# Sheet1.net
KiCad netlist of a schematic drawn in Altium Designer
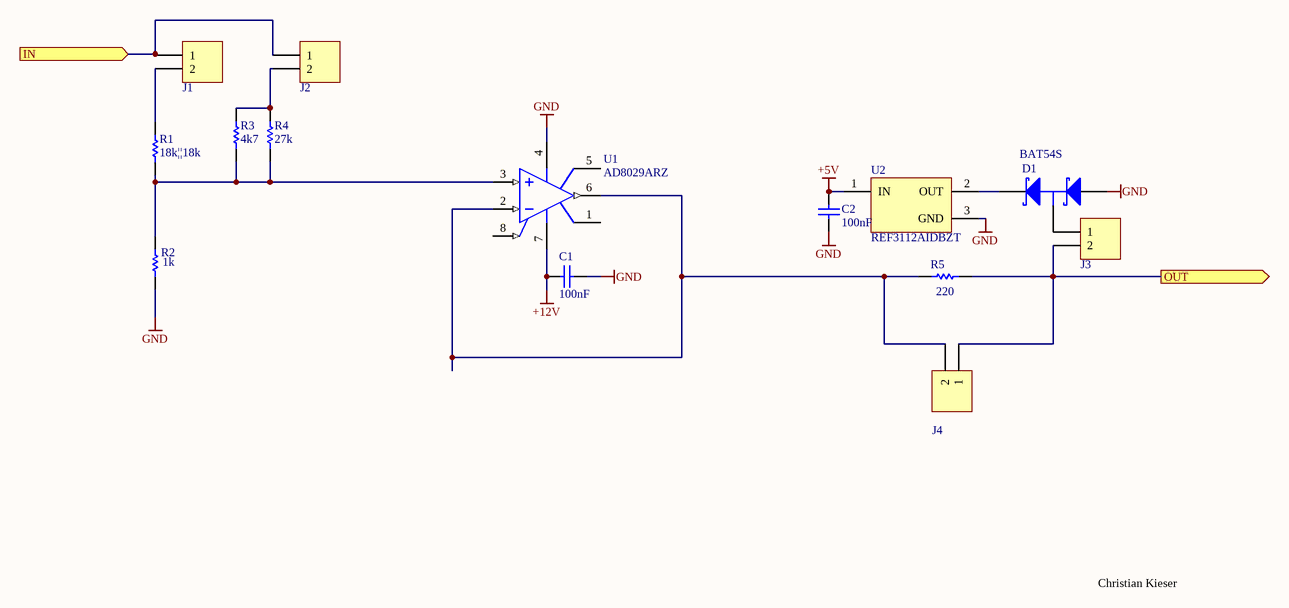
[diagram p0: Sheet1.SchDoc]

(export (version "E")
  (design (tool "Eeschema 10.0.6"))
  (components
    (comp (ref "C1")
      (value "100nF")
      (footprint "CAPC2013X88X50ML20T25")
      (description "generic 0805 COG oder X7R Vielschichtkondensatoren max. +/-10%")
      (libsource (lib "Altium Vault EMBL") (part "CMP-001-0082-2"))
    )
    (comp (ref "C2")
      (value "100nF")
      (footprint "CAPC2013X88X50ML20T25")
      (description "generic 0805 COG oder X7R Vielschichtkondensatoren max. +/-10%")
      (libsource (lib "Altium Vault EMBL") (part "CMP-001-0082-2"))
    )
    (comp (ref "D1")
      (value "BAT54S")
      (footprint "FAIR-SOT23-3_V")
      (description "Schottky Barrier Diode, 30 V, 0.2 A, -55 to 150 degC, 3-Pin SOT23, RoHS, Tape and Reel")
      (fields (field (name "TOLERANCE") "30ppm"))
      (libsource (lib "Altium Vault EMBL 3") (part "DSKY-AKC-3"))
    )
    (comp (ref "J1")
      (value "61300211121")
      (footprint "61300211121")
      (description "2Pol; gerade; WR-PHD 2.54 mm THT Pin Header")
      (fields (field (name "MANUFACTURER") "Wurth Electronics"))
      (libsource (lib "Altium Vault EMBL 3") (part "CMP-001-0071-1"))
    )
    (comp (ref "J2")
      (value "61300211121")
      (footprint "61300211121")
      (description "2Pol; gerade; WR-PHD 2.54 mm THT Pin Header")
      (fields (field (name "MANUFACTURER") "Wurth Electronics"))
      (libsource (lib "Altium Vault EMBL 3") (part "CMP-001-0071-1"))
    )
    (comp (ref "J3")
      (value "61300211121")
      (footprint "61300211121")
      (description "2Pol; gerade; WR-PHD 2.54 mm THT Pin Header")
      (fields (field (name "MANUFACTURER") "Wurth Electronics"))
      (libsource (lib "Altium Vault EMBL 3") (part "CMP-001-0071-1"))
    )
    (comp (ref "J4")
      (value "61300211121")
      (footprint "61300211121")
      (description "2Pol; gerade; WR-PHD 2.54 mm THT Pin Header")
      (fields (field (name "MANUFACTURER") "Wurth Electronics"))
      (libsource (lib "") (part "CMP-001-0071-1_1"))
    )
    (comp (ref "R1")
      (value "18kΖ18k")
      (footprint "YAGO-RC0805_M")
      (description "0805 Yageo Standard BlackBox Resistors")
      (fields (field (name "TOLERANCE") "±1%") (field (name "MANUFACTURER") "Yageo"))
      (libsource (lib "Altium Vault EMBL") (part "CMP-001-0027-2"))
    )
    (comp (ref "R2")
      (value "1k")
      (footprint "YAGO-RC0805_M")
      (description "0805 Yageo Standard BlackBox Resistors")
      (fields (field (name "TOLERANCE") "±1%") (field (name "MANUFACTURER") "Yageo"))
      (libsource (lib "Altium Vault EMBL") (part "CMP-001-0027-2"))
    )
    (comp (ref "R3")
      (value "4k7")
      (footprint "YAGO-RC0805_M")
      (description "0805 Yageo Standard BlackBox Resistors")
      (fields (field (name "TOLERANCE") "±1%") (field (name "MANUFACTURER") "Yageo"))
      (libsource (lib "Altium Vault EMBL") (part "CMP-001-0027-2"))
    )
    (comp (ref "R4")
      (value "27k")
      (footprint "YAGO-RC0805_M")
      (description "0805 Yageo Standard BlackBox Resistors")
      (fields (field (name "TOLERANCE") "±1%") (field (name "MANUFACTURER") "Yageo"))
      (libsource (lib "Altium Vault EMBL") (part "CMP-001-0027-2"))
    )
    (comp (ref "R5")
      (value "220")
      (footprint "YAGO-RC0805_M")
      (description "0805 Yageo Standard BlackBox Resistors")
      (fields (field (name "TOLERANCE") "±1%") (field (name "MANUFACTURER") "Yageo"))
      (libsource (lib "Altium Vault EMBL") (part "CMP-001-0027-2"))
    )
    (comp (ref "U1")
      (value "AD8029ARZ")
      (footprint "ADI-R-8_L")
      (fields (field (name "MANUFACTURER") "Analog Devices") (field (name "GENERIC PART NUMBER") "AD8029"))
      (libsource (lib "Altium Vault EMBL 3") (part "CMP-00480-1"))
    )
    (comp (ref "U2")
      (value "REF3112AIDBZT")
      (footprint "DBZ0003A_N")
      (description "TEXAS INSTRUMENTS - REF3112AIDBZT - VOLTAGE REF, SERIES, 1.25V, SOT-23-3")
      (fields (field (name "MANUFACTURER") "Texas Instruments") (field (name "TOLERANCE") "0.2%"))
      (libsource (lib "Altium Vault EMBL 3") (part "CMP-001-0163-A.1"))
    )
  )
  (nets
    (net (code "1") (name "+5V") (class "Default")
      (node (ref "C2") (pin "1") (pinfunction "1_1") (pintype "passive"))
      (node (ref "U2") (pin "1") (pinfunction "IN_1") (pintype "power_in"))
    )
    (net (code "2") (name "+12V") (class "Default")
      (node (ref "C1") (pin "2") (pinfunction "2_2") (pintype "passive"))
      (node (ref "U1") (pin "7") (pinfunction "+VS_7") (pintype "power_in"))
    )
    (net (code "3") (name "/IN") (class "Default")
      (node (ref "J1") (pin "1") (pinfunction "1_1") (pintype "passive"))
      (node (ref "J2") (pin "1") (pinfunction "1_1") (pintype "passive"))
    )
    (net (code "4") (name "/OUT") (class "Default")
      (node (ref "J3") (pin "2") (pinfunction "2_2") (pintype "passive"))
      (node (ref "J4") (pin "1") (pinfunction "1_1") (pintype "passive"))
      (node (ref "R5") (pin "1") (pinfunction "1_1") (pintype "passive"))
    )
    (net (code "5") (name "GND") (class "Default")
      (node (ref "C1") (pin "1") (pinfunction "1_1") (pintype "passive"))
      (node (ref "C2") (pin "2") (pinfunction "2_2") (pintype "passive"))
      (node (ref "D1") (pin "1") (pinfunction "A_1") (pintype "passive"))
      (node (ref "R2") (pin "1") (pinfunction "1_1") (pintype "passive"))
      (node (ref "U1") (pin "4") (pinfunction "-VS_4") (pintype "power_in"))
      (node (ref "U2") (pin "3") (pinfunction "GND_3") (pintype "power_in"))
    )
    (net (code "6") (name "Net-(D1-C)") (class "Default")
      (node (ref "D1") (pin "3") (pinfunction "C_3") (pintype "passive"))
      (node (ref "J3") (pin "1") (pinfunction "1_1") (pintype "passive"))
    )
    (net (code "7") (name "Net-(D1-K)") (class "Default")
      (node (ref "D1") (pin "2") (pinfunction "K_2") (pintype "passive"))
      (node (ref "U2") (pin "2") (pinfunction "OUT_2") (pintype "power_in"))
    )
    (net (code "8") (name "Net-(J1-Pad2)") (class "Default")
      (node (ref "J1") (pin "2") (pinfunction "2_2") (pintype "passive"))
      (node (ref "R1") (pin "2") (pinfunction "2_2") (pintype "passive"))
    )
    (net (code "9") (name "Net-(J2-Pad2)") (class "Default")
      (node (ref "J2") (pin "2") (pinfunction "2_2") (pintype "passive"))
      (node (ref "R3") (pin "2") (pinfunction "2_2") (pintype "passive"))
      (node (ref "R4") (pin "2") (pinfunction "2_2") (pintype "passive"))
    )
    (net (code "10") (name "Net-(U1-+IN)") (class "Default")
      (node (ref "R1") (pin "1") (pinfunction "1_1") (pintype "passive"))
      (node (ref "R2") (pin "2") (pinfunction "2_2") (pintype "passive"))
      (node (ref "R3") (pin "1") (pinfunction "1_1") (pintype "passive"))
      (node (ref "R4") (pin "1") (pinfunction "1_1") (pintype "passive"))
      (node (ref "U1") (pin "3") (pinfunction "+IN_3") (pintype "input"))
    )
    (net (code "11") (name "Net-(U1--IN)") (class "Default")
      (node (ref "J4") (pin "2") (pinfunction "2_2") (pintype "passive"))
      (node (ref "R5") (pin "2") (pinfunction "2_2") (pintype "passive"))
      (node (ref "U1") (pin "2") (pinfunction "-IN_2") (pintype "input"))
      (node (ref "U1") (pin "6") (pinfunction "VOUT_6") (pintype "output"))
    )
    (net (code "12") (name "unconnected-(U1-NC-Pad1)") (class "Default")
      (node (ref "U1") (pin "1") (pinfunction "NC_1") (pintype "passive"))
    )
    (net (code "13") (name "unconnected-(U1-NC-Pad5)") (class "Default")
      (node (ref "U1") (pin "5") (pinfunction "NC_5") (pintype "passive"))
    )
    (net (code "14") (name "unconnected-(U1-~{DISABLE}-Pad8)") (class "Default")
      (node (ref "U1") (pin "8") (pinfunction "~{DISABLE}_8") (pintype "input"))
    )
  )
)
